# RCD300_USB_DAC_P2.net
KiCad netlist of a schematic drawn in Altium Designer
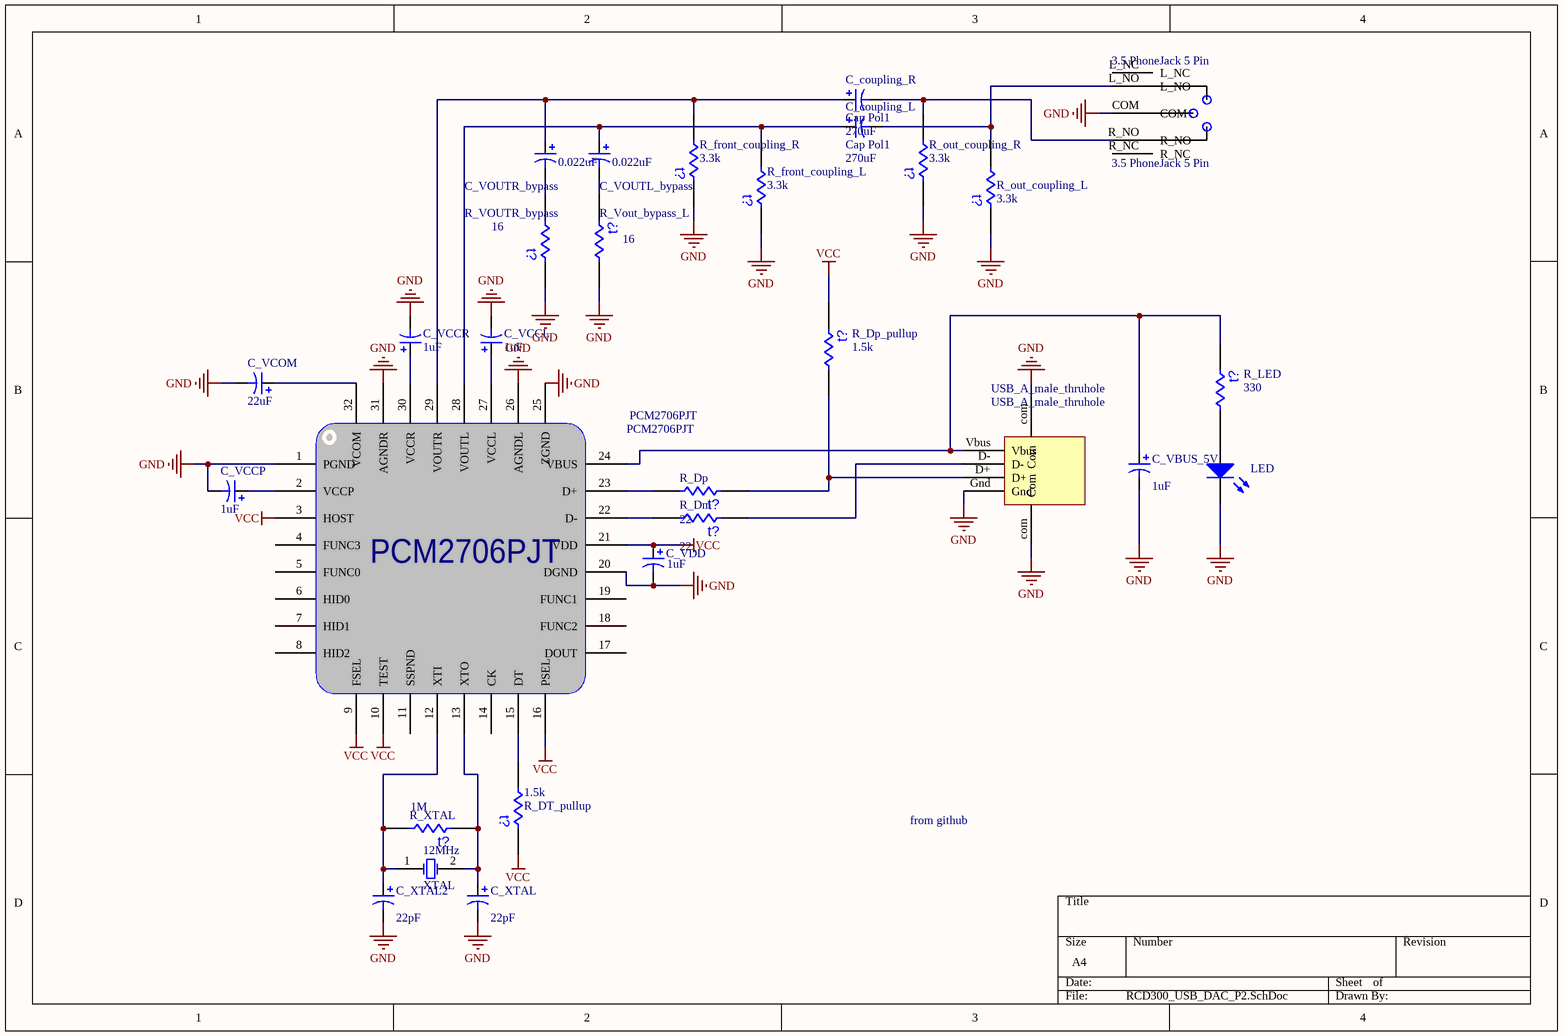
[diagram p0: RCD300_USB_DAC_P2.SchDoc]

(export (version "E")
  (design (tool "Eeschema 10.0.6"))
  (components
    (comp (ref "1.5k")
      (value "R_DT_pullup")
      (footprint "6-0805_N")
      (description "Thermistor")
      (fields (field (name "PUBLISHER") "Altium Limited"))
      (libsource (lib "Miscellaneous Devices") (part "Res Thermal"))
    )
    (comp (ref "3.5 PhoneJack 5 Pin")
      (value "3.5 PhoneJack 5 Pin")
      (footprint "3.5 PhoneJack 5 Pin")
      (libsource (lib "misc") (part "3.5 PhoneJack 5 Pin"))
    )
    (comp (ref "12MHz")
      (value "XTAL")
      (footprint "12MHz Crystal OSC through hole")
      (description "Crystal Oscillator")
      (fields (field (name "PUBLISHER") "Altium Limited"))
      (libsource (lib "Miscellaneous Devices") (part "XTAL"))
    )
    (comp (ref "C_coupling_L")
      (value "Cap Pol1")
      (footprint "CAP_270uf_16V_solid_Aluminum")
      (description "Polarized Capacitor (Radial)")
      (fields (field (name "ALTIUM_VALUE") "270uF") (field (name "PUBLISHER") "Altium Limited"))
      (libsource (lib "Miscellaneous Devices") (part "Cap Pol1"))
    )
    (comp (ref "C_coupling_R")
      (value "Cap Pol1")
      (footprint "CAP_270uf_16V_solid_Aluminum")
      (description "Polarized Capacitor (Radial)")
      (fields (field (name "ALTIUM_VALUE") "270uF") (field (name "PUBLISHER") "Altium Limited"))
      (libsource (lib "Miscellaneous Devices") (part "Cap Pol1"))
    )
    (comp (ref "C_VBUS_5V")
      (value "1uF")
      (footprint "C0805")
      (description "Polarized Capacitor (Surface Mount)")
      (fields (field (name "PUBLISHER") "Altium Limited"))
      (libsource (lib "Miscellaneous Devices") (part "Cap Pol3"))
    )
    (comp (ref "C_VCCL")
      (value "1uF")
      (footprint "C0805")
      (description "Polarized Capacitor (Surface Mount)")
      (fields (field (name "PUBLISHER") "Altium Limited"))
      (libsource (lib "Miscellaneous Devices") (part "Cap Pol3"))
    )
    (comp (ref "C_VCCP")
      (value "1uF")
      (footprint "C0805")
      (description "Polarized Capacitor (Surface Mount)")
      (fields (field (name "PUBLISHER") "Altium Limited"))
      (libsource (lib "Miscellaneous Devices") (part "Cap Pol3"))
    )
    (comp (ref "C_VCCR")
      (value "1uF")
      (footprint "C0805")
      (description "Polarized Capacitor (Surface Mount)")
      (fields (field (name "PUBLISHER") "Altium Limited"))
      (libsource (lib "Miscellaneous Devices") (part "Cap Pol3"))
    )
    (comp (ref "C_VCOM")
      (value "22uF")
      (footprint "CAPC3216N")
      (description "Polarized Capacitor (Surface Mount)")
      (fields (field (name "PUBLISHER") "Altium Limited"))
      (libsource (lib "Miscellaneous Devices") (part "Cap Pol3"))
    )
    (comp (ref "C_VDD")
      (value "1uF")
      (footprint "C0805")
      (description "Polarized Capacitor (Surface Mount)")
      (fields (field (name "PUBLISHER") "Altium Limited"))
      (libsource (lib "Miscellaneous Devices") (part "Cap Pol3"))
    )
    (comp (ref "C_VOUTL_bypass")
      (value "0.022uF")
      (footprint "C0805")
      (description "Polarized Capacitor (Surface Mount)")
      (fields (field (name "PUBLISHER") "Altium Limited"))
      (libsource (lib "Miscellaneous Devices") (part "Cap Pol3"))
    )
    (comp (ref "C_VOUTR_bypass")
      (value "0.022uF")
      (footprint "C0805")
      (description "Polarized Capacitor (Surface Mount)")
      (fields (field (name "PUBLISHER") "Altium Limited"))
      (libsource (lib "Miscellaneous Devices") (part "Cap Pol3"))
    )
    (comp (ref "C_XTAL")
      (value "22pF")
      (footprint "C0805")
      (description "Polarized Capacitor (Surface Mount)")
      (fields (field (name "PUBLISHER") "Altium Limited"))
      (libsource (lib "Miscellaneous Devices") (part "Cap Pol3"))
    )
    (comp (ref "C_XTAL2")
      (value "22pF")
      (footprint "C0805")
      (description "Polarized Capacitor (Surface Mount)")
      (fields (field (name "PUBLISHER") "Altium Limited"))
      (libsource (lib "Miscellaneous Devices") (part "Cap Pol3"))
    )
    (comp (ref "LED")
      (value "~")
      (footprint "CAPC1608N")
      (description "Typical RED, GREEN, YELLOW, AMBER GaAs LED")
      (fields (field (name "PUBLISHER") "Altium Limited"))
      (libsource (lib "Miscellaneous Devices") (part "LED2"))
    )
    (comp (ref "PCM2706PJT")
      (value "PCM2706PJT")
      (footprint "S-PQFP-N32-2mm-out")
      (libsource (lib "misc") (part "PCM2706PJT"))
    )
    (comp (ref "R_Dm")
      (value "22")
      (footprint "6-0805_N")
      (description "Thermistor")
      (fields (field (name "PUBLISHER") "Altium Limited"))
      (libsource (lib "Miscellaneous Devices") (part "Res Thermal"))
    )
    (comp (ref "R_Dp")
      (value "22")
      (footprint "6-0805_N")
      (description "Thermistor")
      (fields (field (name "PUBLISHER") "Altium Limited"))
      (libsource (lib "Miscellaneous Devices") (part "Res Thermal"))
    )
    (comp (ref "R_Dp_pullup")
      (value "1.5k")
      (footprint "6-0805_N")
      (description "Thermistor")
      (fields (field (name "PUBLISHER") "Altium Limited"))
      (libsource (lib "Miscellaneous Devices") (part "Res Thermal"))
    )
    (comp (ref "R_front_coupling_L")
      (value "3.3k")
      (footprint "6-0805_N")
      (description "Thermistor")
      (fields (field (name "PUBLISHER") "Altium Limited"))
      (libsource (lib "Miscellaneous Devices") (part "Res Thermal"))
    )
    (comp (ref "R_front_coupling_R")
      (value "3.3k")
      (footprint "6-0805_N")
      (description "Thermistor")
      (fields (field (name "PUBLISHER") "Altium Limited"))
      (libsource (lib "Miscellaneous Devices") (part "Res Thermal"))
    )
    (comp (ref "R_LED")
      (value "330")
      (footprint "6-0805_N")
      (description "Thermistor")
      (fields (field (name "PUBLISHER") "Altium Limited"))
      (libsource (lib "Miscellaneous Devices") (part "Res Thermal"))
    )
    (comp (ref "R_out_coupling_L")
      (value "3.3k")
      (footprint "6-0805_N")
      (description "Thermistor")
      (fields (field (name "PUBLISHER") "Altium Limited"))
      (libsource (lib "Miscellaneous Devices") (part "Res Thermal"))
    )
    (comp (ref "R_out_coupling_R")
      (value "3.3k")
      (footprint "6-0805_N")
      (description "Thermistor")
      (fields (field (name "PUBLISHER") "Altium Limited"))
      (libsource (lib "Miscellaneous Devices") (part "Res Thermal"))
    )
    (comp (ref "R_VOUTR_bypass")
      (value "16")
      (footprint "6-0805_N")
      (description "Thermistor")
      (fields (field (name "PUBLISHER") "Altium Limited"))
      (libsource (lib "Miscellaneous Devices") (part "Res Thermal"))
    )
    (comp (ref "R_Vout_bypass_L")
      (value "16")
      (footprint "6-0805_N")
      (description "Thermistor")
      (fields (field (name "PUBLISHER") "Altium Limited"))
      (libsource (lib "Miscellaneous Devices") (part "Res Thermal"))
    )
    (comp (ref "R_XTAL")
      (value "1M")
      (footprint "6-0805_N")
      (description "Thermistor")
      (fields (field (name "PUBLISHER") "Altium Limited"))
      (libsource (lib "Miscellaneous Devices") (part "Res Thermal"))
    )
    (comp (ref "USB_A_male_thruhole")
      (value "USB_A_male_thruhole")
      (footprint "USB_A_male_thruhole")
      (libsource (lib "misc") (part "USB_A_male_thruhole"))
    )
  )
  (nets
    (net (code "1") (name "GND") (class "Default")
      (node (ref "3.5 PhoneJack 5 Pin") (pin "COM") (pinfunction "COM_COM") (pintype "passive"))
      (node (ref "C_VBUS_5V") (pin "2") (pinfunction "2_2") (pintype "passive"))
      (node (ref "C_VCCL") (pin "2") (pinfunction "2_2") (pintype "passive"))
      (node (ref "C_VCCP") (pin "2") (pinfunction "2_2") (pintype "passive"))
      (node (ref "C_VCCR") (pin "2") (pinfunction "2_2") (pintype "passive"))
      (node (ref "C_VCOM") (pin "2") (pinfunction "2_2") (pintype "passive"))
      (node (ref "C_VDD") (pin "2") (pinfunction "2_2") (pintype "passive"))
      (node (ref "C_XTAL") (pin "2") (pinfunction "2_2") (pintype "passive"))
      (node (ref "C_XTAL2") (pin "2") (pinfunction "2_2") (pintype "passive"))
      (node (ref "LED") (pin "2") (pinfunction "K_2") (pintype "passive"))
      (node (ref "PCM2706PJT") (pin "1") (pinfunction "PGND_1") (pintype "passive"))
      (node (ref "PCM2706PJT") (pin "20") (pinfunction "DGND_20") (pintype "passive"))
      (node (ref "PCM2706PJT") (pin "25") (pinfunction "ZGND_25") (pintype "passive"))
      (node (ref "PCM2706PJT") (pin "26") (pinfunction "AGNDL_26") (pintype "passive"))
      (node (ref "PCM2706PJT") (pin "31") (pinfunction "AGNDR_31") (pintype "passive"))
      (node (ref "R_VOUTR_bypass") (pin "1") (pinfunction "1_1") (pintype "passive"))
      (node (ref "R_Vout_bypass_L") (pin "2") (pinfunction "2_2") (pintype "passive"))
      (node (ref "R_front_coupling_L") (pin "1") (pinfunction "1_1") (pintype "passive"))
      (node (ref "R_front_coupling_R") (pin "1") (pinfunction "1_1") (pintype "passive"))
      (node (ref "R_out_coupling_L") (pin "1") (pinfunction "1_1") (pintype "passive"))
      (node (ref "R_out_coupling_R") (pin "1") (pinfunction "1_1") (pintype "passive"))
      (node (ref "USB_A_male_thruhole") (pin "Gnd") (pinfunction "Gnd_Gnd") (pintype "passive"))
      (node (ref "USB_A_male_thruhole") (pin "com") (pinfunction "Com_com") (pintype "passive"))
    )
    (net (code "2") (name "Net-(3.5 PhoneJack 5 Pin-PadL_NO)") (class "Default")
      (node (ref "3.5 PhoneJack 5 Pin") (pin "L_NO") (pinfunction "L_NO_L_NO") (pintype "passive"))
      (node (ref "C_coupling_L") (pin "2") (pinfunction "2_2") (pintype "passive"))
      (node (ref "R_out_coupling_L") (pin "2") (pinfunction "2_2") (pintype "passive"))
    )
    (net (code "3") (name "Net-(3.5 PhoneJack 5 Pin-PadR_NO)") (class "Default")
      (node (ref "3.5 PhoneJack 5 Pin") (pin "R_NO") (pinfunction "R_NO_R_NO") (pintype "passive"))
      (node (ref "C_coupling_R") (pin "2") (pinfunction "2_2") (pintype "passive"))
      (node (ref "R_out_coupling_R") (pin "2") (pinfunction "2_2") (pintype "passive"))
    )
    (net (code "4") (name "Net-(12MHz-OSC1)") (class "Default")
      (node (ref "12MHz") (pin "1") (pinfunction "OSC1_1") (pintype "passive"))
      (node (ref "C_XTAL2") (pin "1") (pinfunction "1_1") (pintype "passive"))
      (node (ref "PCM2706PJT") (pin "12") (pinfunction "XTI_12") (pintype "passive"))
      (node (ref "R_XTAL") (pin "2") (pinfunction "2_2") (pintype "passive"))
    )
    (net (code "5") (name "Net-(12MHz-OSC2)") (class "Default")
      (node (ref "12MHz") (pin "2") (pinfunction "OSC2_2") (pintype "passive"))
      (node (ref "C_XTAL") (pin "1") (pinfunction "1_1") (pintype "passive"))
      (node (ref "PCM2706PJT") (pin "13") (pinfunction "XTO_13") (pintype "passive"))
      (node (ref "R_XTAL") (pin "1") (pinfunction "1_1") (pintype "passive"))
    )
    (net (code "6") (name "Net-(C_VOUTL_bypass-Pad2)") (class "Default")
      (node (ref "C_VOUTL_bypass") (pin "2") (pinfunction "2_2") (pintype "passive"))
      (node (ref "R_Vout_bypass_L") (pin "1") (pinfunction "1_1") (pintype "passive"))
    )
    (net (code "7") (name "Net-(C_VOUTR_bypass-Pad2)") (class "Default")
      (node (ref "C_VOUTR_bypass") (pin "2") (pinfunction "2_2") (pintype "passive"))
      (node (ref "R_VOUTR_bypass") (pin "2") (pinfunction "2_2") (pintype "passive"))
    )
    (net (code "8") (name "Net-(LED-A)") (class "Default")
      (node (ref "LED") (pin "1") (pinfunction "A_1") (pintype "passive"))
      (node (ref "R_LED") (pin "2") (pinfunction "2_2") (pintype "passive"))
    )
    (net (code "9") (name "Net-(PCM2706PJT-D+)") (class "Default")
      (node (ref "PCM2706PJT") (pin "23") (pinfunction "D+_23") (pintype "passive"))
      (node (ref "R_Dp") (pin "2") (pinfunction "2_2") (pintype "passive"))
    )
    (net (code "10") (name "Net-(PCM2706PJT-D-)") (class "Default")
      (node (ref "PCM2706PJT") (pin "22") (pinfunction "D-_22") (pintype "passive"))
      (node (ref "R_Dm") (pin "2") (pinfunction "2_2") (pintype "passive"))
    )
    (net (code "11") (name "Net-(PCM2706PJT-DT)") (class "Default")
      (node (ref "1.5k") (pin "2") (pinfunction "2_2") (pintype "passive"))
      (node (ref "PCM2706PJT") (pin "15") (pinfunction "DT_15") (pintype "passive"))
    )
    (net (code "12") (name "Net-(PCM2706PJT-VBUS)") (class "Default")
      (node (ref "C_VBUS_5V") (pin "1") (pinfunction "1_1") (pintype "passive"))
      (node (ref "PCM2706PJT") (pin "24") (pinfunction "VBUS_24") (pintype "passive"))
      (node (ref "R_LED") (pin "1") (pinfunction "1_1") (pintype "passive"))
      (node (ref "USB_A_male_thruhole") (pin "Vbus") (pinfunction "Vbus_Vbus") (pintype "passive"))
    )
    (net (code "13") (name "Net-(PCM2706PJT-VCCL)") (class "Default")
      (node (ref "C_VCCL") (pin "1") (pinfunction "1_1") (pintype "passive"))
      (node (ref "PCM2706PJT") (pin "27") (pinfunction "VCCL_27") (pintype "passive"))
    )
    (net (code "14") (name "Net-(PCM2706PJT-VCCP)") (class "Default")
      (node (ref "C_VCCP") (pin "1") (pinfunction "1_1") (pintype "passive"))
      (node (ref "PCM2706PJT") (pin "2") (pinfunction "VCCP_2") (pintype "passive"))
    )
    (net (code "15") (name "Net-(PCM2706PJT-VCCR)") (class "Default")
      (node (ref "C_VCCR") (pin "1") (pinfunction "1_1") (pintype "passive"))
      (node (ref "PCM2706PJT") (pin "30") (pinfunction "VCCR_30") (pintype "passive"))
    )
    (net (code "16") (name "Net-(PCM2706PJT-VCOM)") (class "Default")
      (node (ref "C_VCOM") (pin "1") (pinfunction "1_1") (pintype "passive"))
      (node (ref "PCM2706PJT") (pin "32") (pinfunction "VCOM_32") (pintype "passive"))
    )
    (net (code "17") (name "Net-(PCM2706PJT-VOUTL)") (class "Default")
      (node (ref "C_VOUTL_bypass") (pin "1") (pinfunction "1_1") (pintype "passive"))
      (node (ref "C_coupling_L") (pin "1") (pinfunction "1_1") (pintype "passive"))
      (node (ref "PCM2706PJT") (pin "28") (pinfunction "VOUTL_28") (pintype "passive"))
      (node (ref "R_front_coupling_L") (pin "2") (pinfunction "2_2") (pintype "passive"))
    )
    (net (code "18") (name "Net-(PCM2706PJT-VOUTR)") (class "Default")
      (node (ref "C_VOUTR_bypass") (pin "1") (pinfunction "1_1") (pintype "passive"))
      (node (ref "C_coupling_R") (pin "1") (pinfunction "1_1") (pintype "passive"))
      (node (ref "PCM2706PJT") (pin "29") (pinfunction "VOUTR_29") (pintype "passive"))
      (node (ref "R_front_coupling_R") (pin "2") (pinfunction "2_2") (pintype "passive"))
    )
    (net (code "19") (name "Net-(R_Dm-Pad1)") (class "Default")
      (node (ref "R_Dm") (pin "1") (pinfunction "1_1") (pintype "passive"))
      (node (ref "USB_A_male_thruhole") (pin "D-") (pinfunction "D-_D-") (pintype "passive"))
    )
    (net (code "20") (name "Net-(R_Dp-Pad1)") (class "Default")
      (node (ref "R_Dp") (pin "1") (pinfunction "1_1") (pintype "passive"))
      (node (ref "R_Dp_pullup") (pin "2") (pinfunction "2_2") (pintype "passive"))
      (node (ref "USB_A_male_thruhole") (pin "D+") (pinfunction "D+_D+") (pintype "passive"))
    )
    (net (code "21") (name "VCC") (class "Default")
      (node (ref "1.5k") (pin "1") (pinfunction "1_1") (pintype "passive"))
      (node (ref "C_VDD") (pin "1") (pinfunction "1_1") (pintype "passive"))
      (node (ref "PCM2706PJT") (pin "10") (pinfunction "TEST_10") (pintype "passive"))
      (node (ref "PCM2706PJT") (pin "16") (pinfunction "PSEL_16") (pintype "passive"))
      (node (ref "PCM2706PJT") (pin "21") (pinfunction "VDD_21") (pintype "passive"))
      (node (ref "PCM2706PJT") (pin "3") (pinfunction "HOST_3") (pintype "passive"))
      (node (ref "PCM2706PJT") (pin "9") (pinfunction "FSEL_9") (pintype "passive"))
      (node (ref "R_Dp_pullup") (pin "1") (pinfunction "1_1") (pintype "passive"))
    )
    (net (code "22") (name "unconnected-(3.5 PhoneJack 5 Pin-PadL_NC)") (class "Default")
      (node (ref "3.5 PhoneJack 5 Pin") (pin "L_NC") (pinfunction "L_NC_L_NC") (pintype "passive"))
    )
    (net (code "23") (name "unconnected-(3.5 PhoneJack 5 Pin-PadR_NC)") (class "Default")
      (node (ref "3.5 PhoneJack 5 Pin") (pin "R_NC") (pinfunction "R_NC_R_NC") (pintype "passive"))
    )
    (net (code "24") (name "unconnected-(PCM2706PJT-CK-Pad14)") (class "Default")
      (node (ref "PCM2706PJT") (pin "14") (pinfunction "CK_14") (pintype "passive"))
    )
    (net (code "25") (name "unconnected-(PCM2706PJT-DOUT-Pad17)") (class "Default")
      (node (ref "PCM2706PJT") (pin "17") (pinfunction "DOUT_17") (pintype "passive"))
    )
    (net (code "26") (name "unconnected-(PCM2706PJT-FUNC0-Pad5)") (class "Default")
      (node (ref "PCM2706PJT") (pin "5") (pinfunction "FUNC0_5") (pintype "passive"))
    )
    (net (code "27") (name "unconnected-(PCM2706PJT-FUNC1-Pad19)") (class "Default")
      (node (ref "PCM2706PJT") (pin "19") (pinfunction "FUNC1_19") (pintype "passive"))
    )
    (net (code "28") (name "unconnected-(PCM2706PJT-FUNC2-Pad18)") (class "Default")
      (node (ref "PCM2706PJT") (pin "18") (pinfunction "FUNC2_18") (pintype "passive"))
    )
    (net (code "29") (name "unconnected-(PCM2706PJT-FUNC3-Pad4)") (class "Default")
      (node (ref "PCM2706PJT") (pin "4") (pinfunction "FUNC3_4") (pintype "passive"))
    )
    (net (code "30") (name "unconnected-(PCM2706PJT-HID0-Pad6)") (class "Default")
      (node (ref "PCM2706PJT") (pin "6") (pinfunction "HID0_6") (pintype "passive"))
    )
    (net (code "31") (name "unconnected-(PCM2706PJT-HID1-Pad7)") (class "Default")
      (node (ref "PCM2706PJT") (pin "7") (pinfunction "HID1_7") (pintype "passive"))
    )
    (net (code "32") (name "unconnected-(PCM2706PJT-HID2-Pad8)") (class "Default")
      (node (ref "PCM2706PJT") (pin "8") (pinfunction "HID2_8") (pintype "passive"))
    )
    (net (code "33") (name "unconnected-(PCM2706PJT-SSPND-Pad11)") (class "Default")
      (node (ref "PCM2706PJT") (pin "11") (pinfunction "SSPND_11") (pintype "passive"))
    )
  )
)
